# Servo_decoup.net
KiCad netlist of a schematic drawn in EAGLE
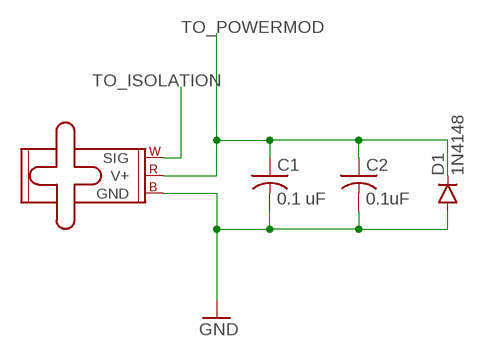
[diagram p0: schematic, sheet 1]

(export (version "E")
  (design (tool "Eeschema 10.0.6"))
  (components
    (comp (ref "C1")
      (value "0.1 uF")
      (footprint "eagle-import:C025-025X050")
      (libsource (lib "eagle-import") (part "C-US025-025X050"))
    )
    (comp (ref "C2")
      (value "0.1uF")
      (footprint "eagle-import:C025-025X050")
      (libsource (lib "eagle-import") (part "C-US025-025X050"))
    )
    (comp (ref "D1")
      (value "1N4148")
      (footprint "eagle-import:DIODE-1N4148")
      (libsource (lib "eagle-import") (part "DIODE1N4148"))
    )
    (comp (ref "M1")
      (value "SMALL_SERVO")
      (footprint "eagle-import:1X03")
      (libsource (lib "eagle-import") (part "SMALL_SERVO"))
    )
  )
  (nets
    (net (code "1") (name "/TO_ISOLATION") (class "Default")
      (node (ref "M1") (pin "1") (pinfunction "SIG_1") (pintype "bidirectional"))
    )
    (net (code "2") (name "/TO_POWERMOD") (class "Default")
      (node (ref "C1") (pin "1") (pinfunction "1_1") (pintype "passive"))
      (node (ref "C2") (pin "1") (pinfunction "1_1") (pintype "passive"))
      (node (ref "D1") (pin "C") (pinfunction "C_C") (pintype "passive"))
      (node (ref "M1") (pin "2") (pinfunction "V+_2") (pintype "bidirectional"))
    )
    (net (code "3") (name "GND") (class "Default")
      (node (ref "C1") (pin "2") (pinfunction "2_2") (pintype "passive"))
      (node (ref "C2") (pin "2") (pinfunction "2_2") (pintype "passive"))
      (node (ref "D1") (pin "A") (pinfunction "A_A") (pintype "passive"))
      (node (ref "M1") (pin "3") (pinfunction "GND_3") (pintype "bidirectional"))
    )
  )
)
